# brightness_control.net
KiCad netlist of a schematic drawn in EAGLE
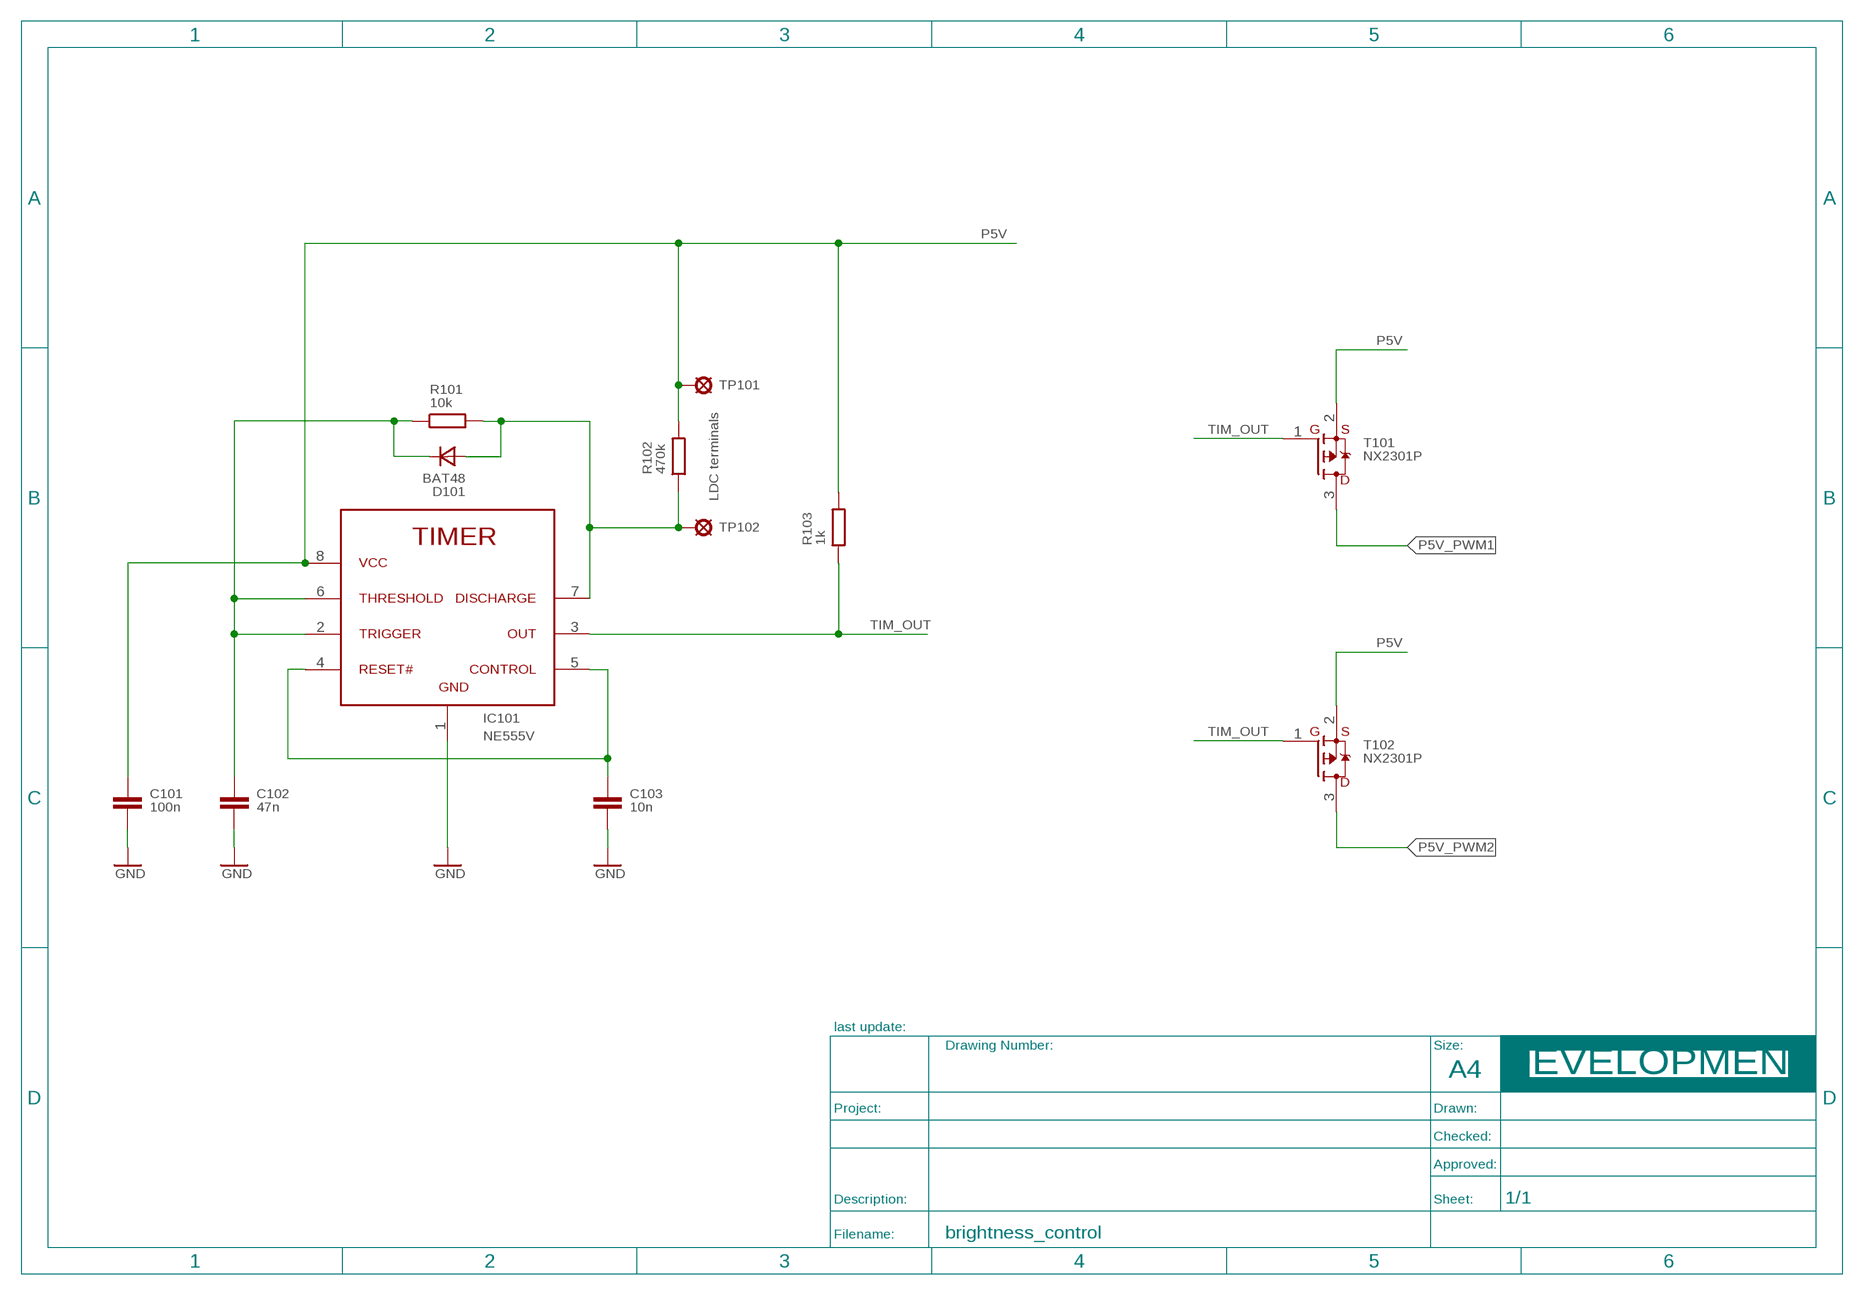
[diagram p0: schematic, sheet 1]

(export (version "E")
  (design (tool "Eeschema 10.0.6"))
  (components
    (comp (ref "C101")
      (value "100n")
      (footprint "eagle-import:S_0805")
      (fields (field (name "PART_CODE_BEL") "C_PAC_S_0805_VAL_100n"))
      (libsource (lib "eagle-import") (part "C_EU_S_0805"))
    )
    (comp (ref "C102")
      (value "47n")
      (footprint "eagle-import:S_0805")
      (fields (field (name "PART_CODE_BEL") "C_PAC_S_0805_VAL_47n"))
      (libsource (lib "eagle-import") (part "C_EU_S_0805"))
    )
    (comp (ref "C103")
      (value "10n")
      (footprint "eagle-import:S_0805")
      (fields (field (name "PART_CODE_BEL") "C_PAC_S_0805_VAL_10n"))
      (libsource (lib "eagle-import") (part "C_EU_S_0805"))
    )
    (comp (ref "D101")
      (value "BAT48")
      (footprint "eagle-import:T_DO204_GRID_10MM")
      (libsource (lib "eagle-import") (part "SINGLE_T_DO204/10"))
    )
    (comp (ref "IC101")
      (value "NE555V")
      (footprint "eagle-import:T_NDIP8")
      (fields (field (name "PART_CODE_BEL") "IC_PAC_T_NDIP8_VAL_NE555V"))
      (libsource (lib "eagle-import") (part "555P"))
    )
    (comp (ref "R101")
      (value "10k")
      (footprint "eagle-import:S_0805")
      (fields (field (name "PART_CODE_BEL") "R_PAC_S_0805_VAL_10k"))
      (libsource (lib "eagle-import") (part "R_EU_S_0805"))
    )
    (comp (ref "R102")
      (value "470k")
      (footprint "eagle-import:S_0805")
      (fields (field (name "PART_CODE_BEL") "R_PAC_S_0805_VAL_470k"))
      (libsource (lib "eagle-import") (part "R_EU_S_0805"))
    )
    (comp (ref "R103")
      (value "1k")
      (footprint "eagle-import:S_0805")
      (fields (field (name "PART_CODE_BEL") "R_PAC_S_0805_VAL_1k"))
      (libsource (lib "eagle-import") (part "R_EU_S_0805"))
    )
    (comp (ref "T101")
      (value "NX2301P")
      (footprint "eagle-import:S_SOT23")
      (fields (field (name "PART_CODE_BEL") "T_PAC_S_SOT23_VAL_NX2301P"))
      (libsource (lib "eagle-import") (part "P-MOSFET"))
    )
    (comp (ref "T102")
      (value "NX2301P")
      (footprint "eagle-import:S_SOT23")
      (fields (field (name "PART_CODE_BEL") "T_PAC_S_SOT23_VAL_NX2301P"))
      (libsource (lib "eagle-import") (part "P-MOSFET"))
    )
    (comp (ref "TP101")
      (value "TEST_POINT_T_LARGE")
      (footprint "eagle-import:T_TEST_POINT_LARGE")
      (libsource (lib "eagle-import") (part "TEST_POINT_T_LARGE"))
    )
    (comp (ref "TP102")
      (value "TEST_POINT_T_LARGE")
      (footprint "eagle-import:T_TEST_POINT_LARGE")
      (libsource (lib "eagle-import") (part "TEST_POINT_T_LARGE"))
    )
  )
  (nets
    (net (code "1") (name "/P5V") (class "Default")
      (node (ref "C101") (pin "1") (pinfunction "1_1") (pintype "passive"))
      (node (ref "IC101") (pin "8") (pinfunction "VCC_8") (pintype "power_in"))
      (node (ref "R102") (pin "2") (pinfunction "2_2") (pintype "passive"))
      (node (ref "R103") (pin "2") (pinfunction "2_2") (pintype "passive"))
      (node (ref "T101") (pin "2") (pinfunction "S_2") (pintype "passive"))
      (node (ref "T102") (pin "2") (pinfunction "S_2") (pintype "passive"))
      (node (ref "TP101") (pin "1") (pinfunction "MP_1") (pintype "passive"))
    )
    (net (code "2") (name "/TIM_OUT") (class "Default")
      (node (ref "IC101") (pin "3") (pinfunction "OUT_3") (pintype "output"))
      (node (ref "R103") (pin "1") (pinfunction "1_1") (pintype "passive"))
      (node (ref "T101") (pin "1") (pinfunction "G_1") (pintype "passive"))
      (node (ref "T102") (pin "1") (pinfunction "G_1") (pintype "passive"))
    )
    (net (code "3") (name "GND") (class "Default")
      (node (ref "C101") (pin "2") (pinfunction "2_2") (pintype "passive"))
      (node (ref "C102") (pin "2") (pinfunction "2_2") (pintype "passive"))
      (node (ref "C103") (pin "2") (pinfunction "2_2") (pintype "passive"))
      (node (ref "IC101") (pin "1") (pinfunction "GND_1") (pintype "power_in"))
    )
    (net (code "4") (name "Net-(IC101-DSCHRG)") (class "Default")
      (node (ref "D101") (pin "A") (pinfunction "A_A") (pintype "passive"))
      (node (ref "IC101") (pin "7") (pinfunction "DSCHRG_7") (pintype "output"))
      (node (ref "R101") (pin "2") (pinfunction "2_2") (pintype "passive"))
      (node (ref "R102") (pin "1") (pinfunction "1_1") (pintype "passive"))
      (node (ref "TP102") (pin "1") (pinfunction "MP_1") (pintype "passive"))
    )
    (net (code "5") (name "Net-(IC101-OC)") (class "Default")
      (node (ref "C103") (pin "1") (pinfunction "1_1") (pintype "passive"))
      (node (ref "IC101") (pin "4") (pinfunction "RST#_4") (pintype "input"))
      (node (ref "IC101") (pin "5") (pinfunction "OC_5") (pintype "passive"))
    )
    (net (code "6") (name "Net-(IC101-TRG)") (class "Default")
      (node (ref "C102") (pin "1") (pinfunction "1_1") (pintype "passive"))
      (node (ref "D101") (pin "C") (pinfunction "C_C") (pintype "passive"))
      (node (ref "IC101") (pin "2") (pinfunction "TRG_2") (pintype "passive"))
      (node (ref "IC101") (pin "6") (pinfunction "TRSHLD_6") (pintype "passive"))
      (node (ref "R101") (pin "1") (pinfunction "1_1") (pintype "passive"))
    )
    (net (code "7") (name "P5V_PWM1") (class "Default")
      (node (ref "T101") (pin "3") (pinfunction "D_3") (pintype "passive"))
    )
    (net (code "8") (name "P5V_PWM2") (class "Default")
      (node (ref "T102") (pin "3") (pinfunction "D_3") (pintype "passive"))
    )
  )
)
